# interface-switches.net
KiCad netlist of a schematic drawn in Altium Designer
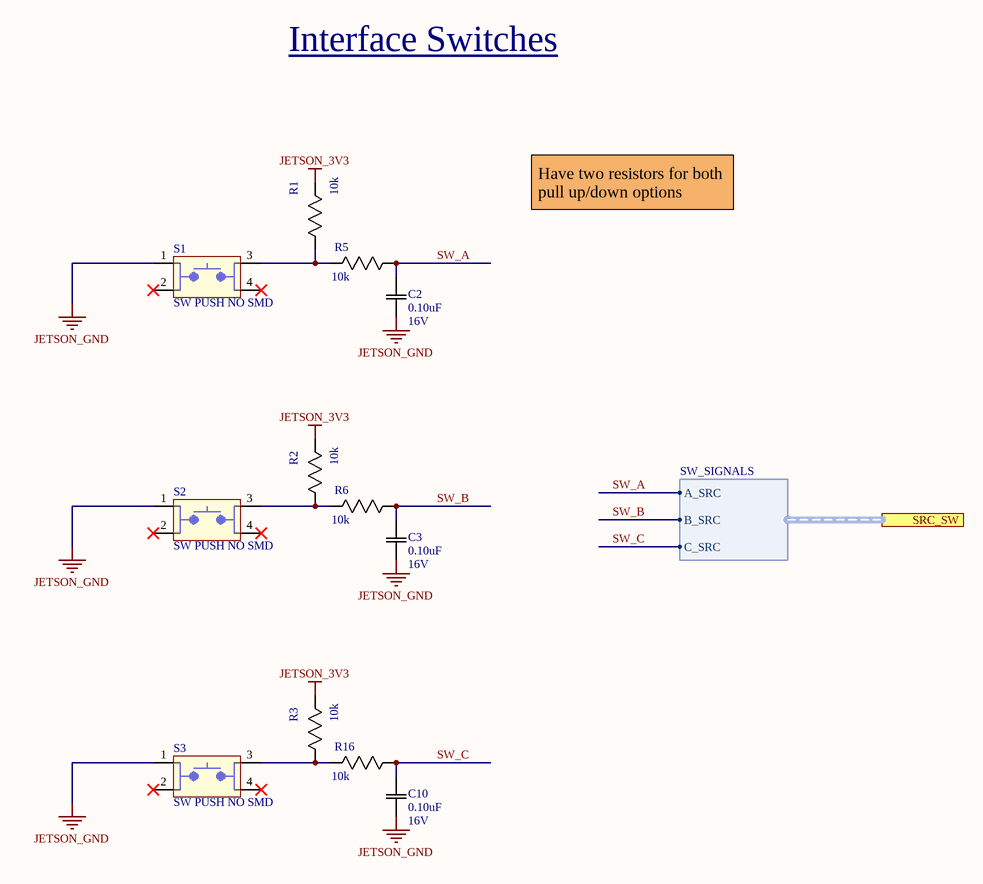
[diagram p0: interface-switches.SchDoc]

(export (version "E")
  (design (tool "Eeschema 10.0.6"))
  (components
    (comp (ref "C2")
      (value "0.10uF")
      (footprint "0603")
      (description "CAP CER 0.10UF 16V X5R 0603")
      (fields
        (field (name "TOLERANCE") "10%")
        (field (name "RATING") "16V")
        (field (name "PART NUMBER") "CAP 0.10uF 16V")
      )
      (libsource (lib "capacitor_library") (part "CAP 0.10uF 16V"))
    )
    (comp (ref "C3")
      (value "0.10uF")
      (footprint "0603")
      (description "CAP CER 0.10UF 16V X5R 0603")
      (fields
        (field (name "TOLERANCE") "10%")
        (field (name "RATING") "16V")
        (field (name "PART NUMBER") "CAP 0.10uF 16V")
      )
      (libsource (lib "capacitor_library") (part "CAP 0.10uF 16V"))
    )
    (comp (ref "C10")
      (value "0.10uF")
      (footprint "0603")
      (description "CAP CER 0.10UF 16V X5R 0603")
      (fields
        (field (name "TOLERANCE") "10%")
        (field (name "RATING") "16V")
        (field (name "PART NUMBER") "CAP 0.10uF 16V")
      )
      (libsource (lib "capacitor_library") (part "CAP 0.10uF 16V"))
    )
    (comp (ref "R1")
      (value "10k")
      (footprint "0603")
      (description "RES SMD 10K OHM 5% 1/8W 0805")
      (fields (field (name "TOLERANCE") "5%") (field (name "PART NUMBER") "RES 10k 1/8W - 5%"))
      (libsource (lib "Resistor_Library") (part "RES 10k 1/8W 5%"))
    )
    (comp (ref "R2")
      (value "10k")
      (footprint "0603")
      (description "RES SMD 10K OHM 5% 1/8W 0805")
      (fields (field (name "TOLERANCE") "5%") (field (name "PART NUMBER") "RES 10k 1/8W - 5%"))
      (libsource (lib "Resistor_Library") (part "RES 10k 1/8W 5%"))
    )
    (comp (ref "R3")
      (value "10k")
      (footprint "0603")
      (description "RES SMD 10K OHM 5% 1/8W 0805")
      (fields (field (name "TOLERANCE") "5%") (field (name "PART NUMBER") "RES 10k 1/8W - 5%"))
      (libsource (lib "Resistor_Library") (part "RES 10k 1/8W 5%"))
    )
    (comp (ref "R5")
      (value "10k")
      (footprint "0603")
      (description "RES SMD 10K OHM 5% 1/8W 0805")
      (fields (field (name "TOLERANCE") "5%") (field (name "PART NUMBER") "RES 10k 1/8W - 5%"))
      (libsource (lib "Resistor_Library") (part "RES 10k 1/8W 5%"))
    )
    (comp (ref "R6")
      (value "10k")
      (footprint "0603")
      (description "RES SMD 10K OHM 5% 1/8W 0805")
      (fields (field (name "TOLERANCE") "5%") (field (name "PART NUMBER") "RES 10k 1/8W - 5%"))
      (libsource (lib "Resistor_Library") (part "RES 10k 1/8W 5%"))
    )
    (comp (ref "R16")
      (value "10k")
      (footprint "0603")
      (description "RES SMD 10K OHM 5% 1/8W 0805")
      (fields (field (name "TOLERANCE") "5%") (field (name "PART NUMBER") "RES 10k 1/8W - 5%"))
      (libsource (lib "Resistor_Library") (part "RES 10k 1/8W 5%"))
    )
    (comp (ref "S1")
      (value "SW PUSH NO SMD")
      (footprint "TL3305")
      (description "Switch Tactile N.O. SPST Round Button Gull Wing 0.05A 12VDC 2.55N SMD T/R")
      (libsource (lib "Switch_Library") (part "SW PUSH NO SMD"))
    )
    (comp (ref "S2")
      (value "SW PUSH NO SMD")
      (footprint "TL3305")
      (description "Switch Tactile N.O. SPST Round Button Gull Wing 0.05A 12VDC 2.55N SMD T/R")
      (libsource (lib "Switch_Library") (part "SW PUSH NO SMD"))
    )
    (comp (ref "S3")
      (value "SW PUSH NO SMD")
      (footprint "TL3305")
      (description "Switch Tactile N.O. SPST Round Button Gull Wing 0.05A 12VDC 2.55N SMD T/R")
      (libsource (lib "Switch_Library") (part "SW PUSH NO SMD"))
    )
  )
  (nets
    (net (code "2") (name "/SW_A") (class "Default")
      (node (ref "C2") (pin "2") (pinfunction "C2_2") (pintype "passive"))
      (node (ref "R5") (pin "1") (pinfunction "R1_1") (pintype "passive"))
    )
    (net (code "3") (name "/SW_B") (class "Default")
      (node (ref "C3") (pin "2") (pinfunction "C2_2") (pintype "passive"))
      (node (ref "R6") (pin "1") (pinfunction "R1_1") (pintype "passive"))
    )
    (net (code "4") (name "/SW_C") (class "Default")
      (node (ref "C10") (pin "2") (pinfunction "C2_2") (pintype "passive"))
      (node (ref "R16") (pin "1") (pinfunction "R1_1") (pintype "passive"))
    )
    (net (code "6") (name "JETSON_3V3") (class "Default")
      (node (ref "R1") (pin "1") (pinfunction "R1_1") (pintype "passive"))
      (node (ref "R2") (pin "1") (pinfunction "R1_1") (pintype "passive"))
      (node (ref "R3") (pin "1") (pinfunction "R1_1") (pintype "passive"))
    )
    (net (code "7") (name "JETSON_GND") (class "Default")
      (node (ref "C10") (pin "1") (pinfunction "C1_1") (pintype "passive"))
      (node (ref "C2") (pin "1") (pinfunction "C1_1") (pintype "passive"))
      (node (ref "C3") (pin "1") (pinfunction "C1_1") (pintype "passive"))
      (node (ref "S1") (pin "1") (pinfunction "1_1") (pintype "passive"))
      (node (ref "S2") (pin "1") (pinfunction "1_1") (pintype "passive"))
      (node (ref "S3") (pin "1") (pinfunction "1_1") (pintype "passive"))
    )
    (net (code "8") (name "Net-(R1-R2)") (class "Default")
      (node (ref "R1") (pin "2") (pinfunction "R2_2") (pintype "passive"))
      (node (ref "R5") (pin "2") (pinfunction "R2_2") (pintype "passive"))
      (node (ref "S1") (pin "3") (pinfunction "3_3") (pintype "passive"))
    )
    (net (code "9") (name "Net-(R2-R2)") (class "Default")
      (node (ref "R2") (pin "2") (pinfunction "R2_2") (pintype "passive"))
      (node (ref "R6") (pin "2") (pinfunction "R2_2") (pintype "passive"))
      (node (ref "S2") (pin "3") (pinfunction "3_3") (pintype "passive"))
    )
    (net (code "10") (name "Net-(R16-R2)") (class "Default")
      (node (ref "R16") (pin "2") (pinfunction "R2_2") (pintype "passive"))
      (node (ref "R3") (pin "2") (pinfunction "R2_2") (pintype "passive"))
      (node (ref "S3") (pin "3") (pinfunction "3_3") (pintype "passive"))
    )
    (net (code "11") (name "unconnected-(S1-Pad2)") (class "Default")
      (node (ref "S1") (pin "2") (pinfunction "2_2") (pintype "passive+no_connect"))
    )
    (net (code "12") (name "unconnected-(S1-Pad4)") (class "Default")
      (node (ref "S1") (pin "4") (pinfunction "4_4") (pintype "passive+no_connect"))
    )
    (net (code "13") (name "unconnected-(S2-Pad2)") (class "Default")
      (node (ref "S2") (pin "2") (pinfunction "2_2") (pintype "passive+no_connect"))
    )
    (net (code "14") (name "unconnected-(S2-Pad4)") (class "Default")
      (node (ref "S2") (pin "4") (pinfunction "4_4") (pintype "passive+no_connect"))
    )
    (net (code "15") (name "unconnected-(S3-Pad2)") (class "Default")
      (node (ref "S3") (pin "2") (pinfunction "2_2") (pintype "passive+no_connect"))
    )
    (net (code "16") (name "unconnected-(S3-Pad4)") (class "Default")
      (node (ref "S3") (pin "4") (pinfunction "4_4") (pintype "passive+no_connect"))
    )
  )
)
